# new_power2.net
KiCad netlist of a schematic drawn in EAGLE
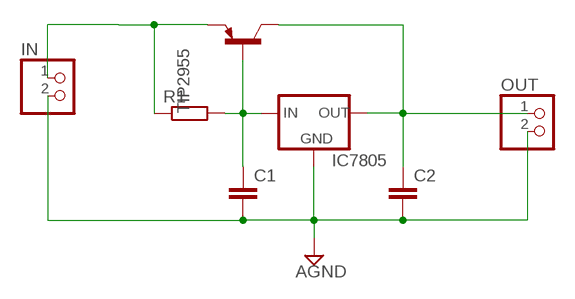
[diagram p0: schematic, sheet 1]

(export (version "E")
  (design (tool "Eeschema 10.0.6"))
  (components
    (comp (ref "C1")
      (value "C-EU025-024X044")
      (footprint "eagle-import:C025-024X044")
      (libsource (lib "eagle-import") (part "C-EU025-024X044"))
    )
    (comp (ref "C2")
      (value "C-EU025-024X044")
      (footprint "eagle-import:C025-024X044")
      (libsource (lib "eagle-import") (part "C-EU025-024X044"))
    )
    (comp (ref "IC7805")
      (value "78XXL")
      (footprint "eagle-import:78XXL")
      (libsource (lib "eagle-import") (part "78XXL"))
    )
    (comp (ref "IN")
      (value "PINHD-1X2")
      (footprint "eagle-import:1X02")
      (libsource (lib "eagle-import") (part "PINHD-1X2"))
    )
    (comp (ref "OUT")
      (value "PINHD-1X2")
      (footprint "eagle-import:1X02")
      (libsource (lib "eagle-import") (part "PINHD-1X2"))
    )
    (comp (ref "R1")
      (value "R-EU_0204/5")
      (footprint "eagle-import:0204_5")
      (libsource (lib "eagle-import") (part "R-EU_0204/5"))
    )
    (comp (ref "TIP2955")
      (value "-PNP-TO220")
      (footprint "eagle-import:TO220")
      (libsource (lib "eagle-import") (part "-PNP-TO220"))
    )
  )
  (nets
    (net (code "1") (name "AGND") (class "Default")
      (node (ref "C1") (pin "2") (pinfunction "2_2") (pintype "passive"))
      (node (ref "C2") (pin "2") (pinfunction "2_2") (pintype "passive"))
      (node (ref "IC7805") (pin "GND") (pinfunction "GND_GND") (pintype "input"))
      (node (ref "IN") (pin "2") (pinfunction "2_2") (pintype "passive"))
      (node (ref "OUT") (pin "2") (pinfunction "2_2") (pintype "passive"))
    )
    (net (code "2") (name "Net-(TIP2955-B)") (class "Default")
      (node (ref "C1") (pin "1") (pinfunction "1_1") (pintype "passive"))
      (node (ref "IC7805") (pin "IN") (pinfunction "IN_IN") (pintype "input"))
      (node (ref "R1") (pin "2") (pinfunction "2_2") (pintype "passive"))
      (node (ref "TIP2955") (pin "1") (pinfunction "B_1") (pintype "passive"))
    )
    (net (code "3") (name "Net-(TIP2955-C)") (class "Default")
      (node (ref "C2") (pin "1") (pinfunction "1_1") (pintype "passive"))
      (node (ref "IC7805") (pin "OUT") (pinfunction "OUT_OUT") (pintype "passive"))
      (node (ref "OUT") (pin "1") (pinfunction "1_1") (pintype "passive"))
      (node (ref "TIP2955") (pin "2") (pinfunction "C_2") (pintype "passive"))
    )
    (net (code "4") (name "Net-(TIP2955-E)") (class "Default")
      (node (ref "IN") (pin "1") (pinfunction "1_1") (pintype "passive"))
      (node (ref "R1") (pin "1") (pinfunction "1_1") (pintype "passive"))
      (node (ref "TIP2955") (pin "3") (pinfunction "E_3") (pintype "passive"))
    )
  )
)
